# 02A-003.net
KiCad netlist of a schematic drawn in EAGLE
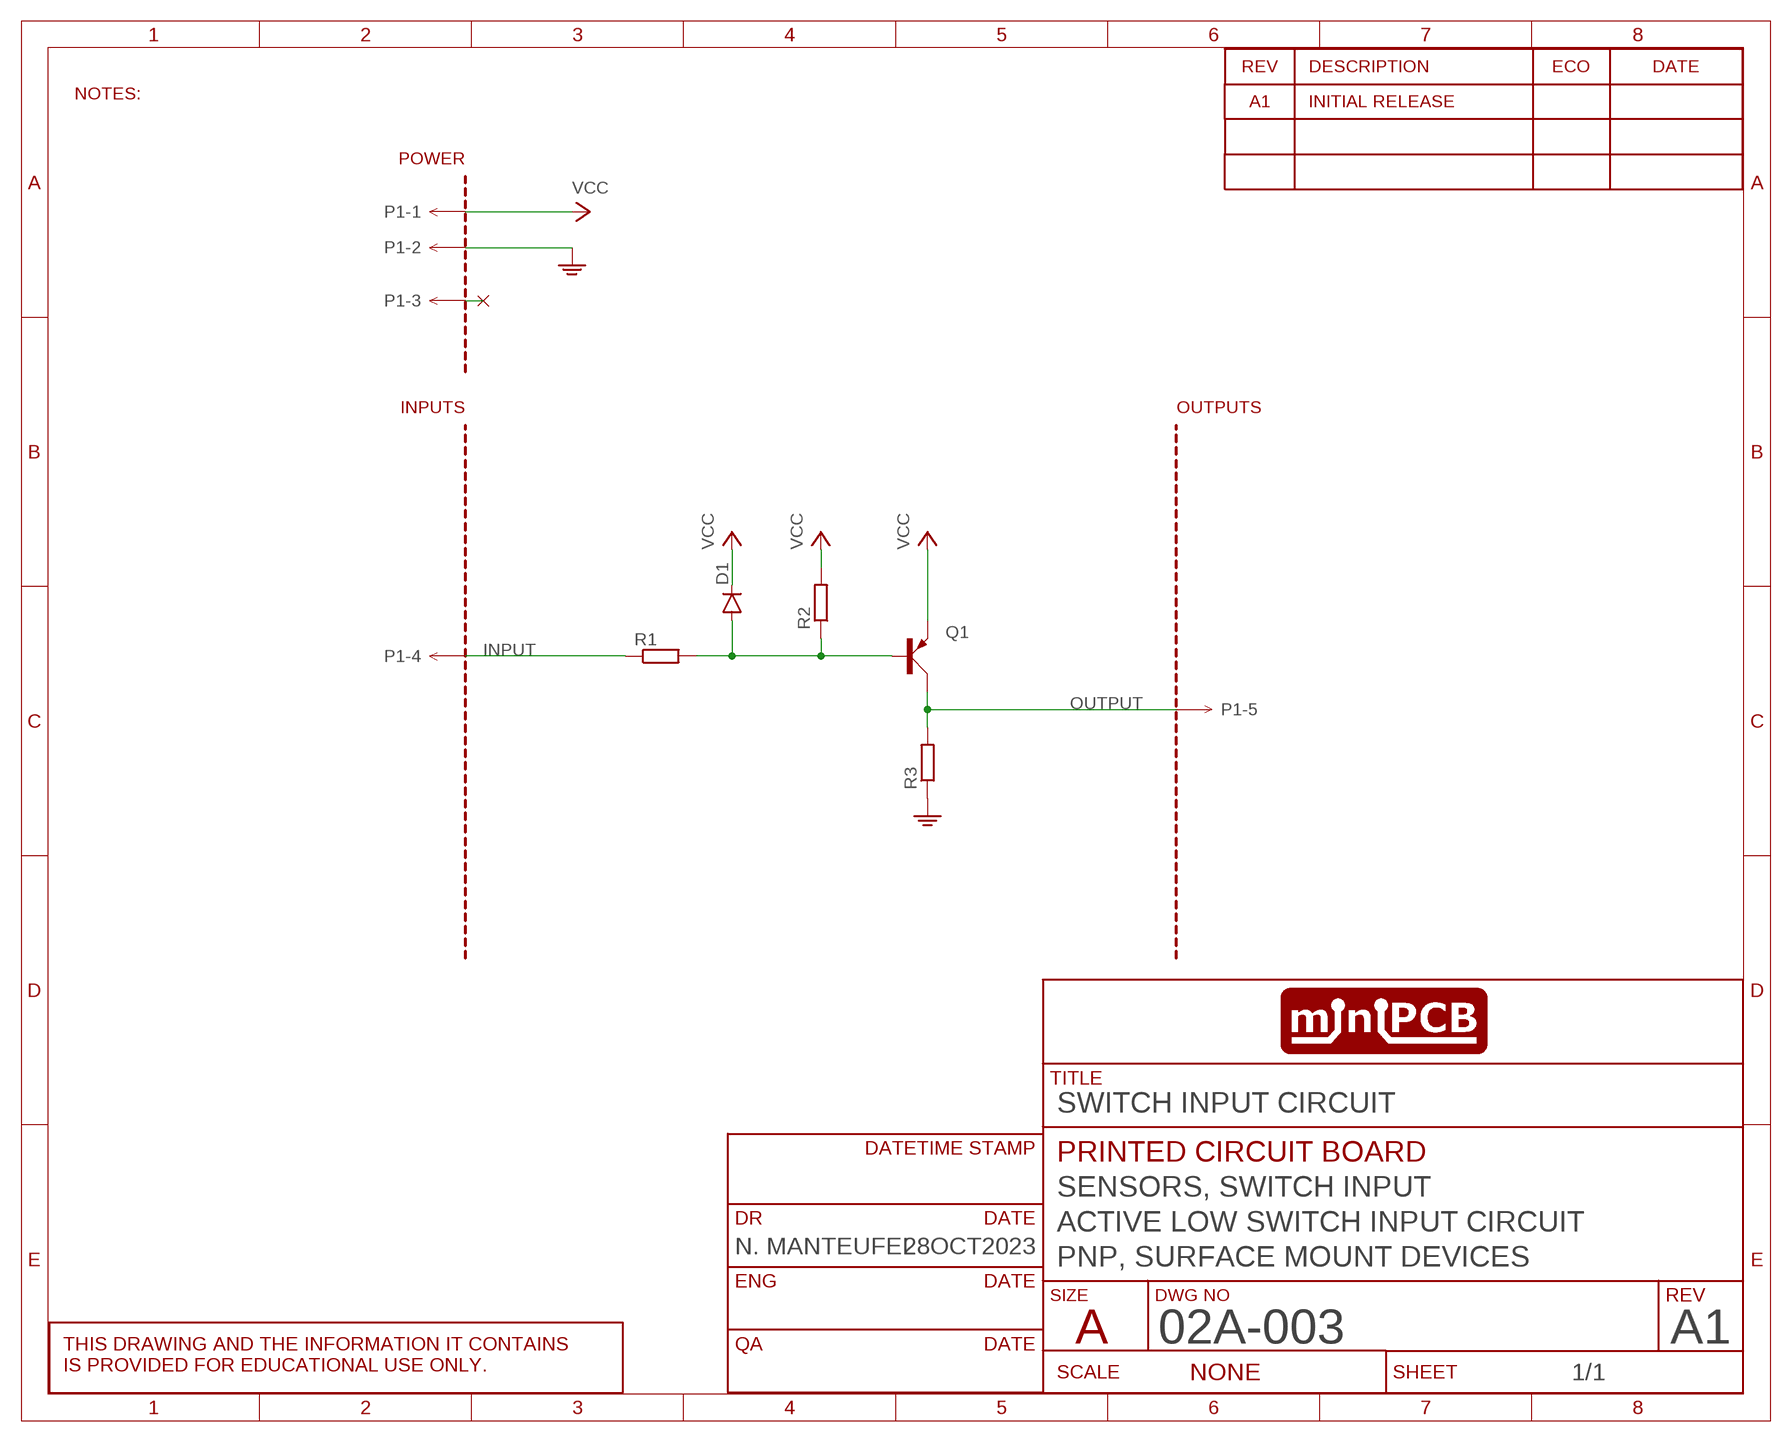
[diagram p0: schematic, sheet 1]

(export (version "E")
  (design (tool "Eeschema 10.0.6"))
  (components
    (comp (ref "D1")
      (value "DIODESMD")
      (footprint "eagle-import:DO214AC")
      (libsource (lib "eagle-import") (part "DIODESMD"))
    )
    (comp (ref "P1")
      (value "MINIPCB_5P5P")
      (footprint "eagle-import:PINS_1X5")
      (libsource (lib "eagle-import") (part "MINIPCB_5P5P"))
    )
    (comp (ref "PCB1")
      (value "MINIPCB_0P00A-20X25")
      (footprint "eagle-import:MINIPCB_00A_20X25")
      (fields (field (name "PART_NUMBER") "02A-003"))
      (libsource (lib "eagle-import") (part "MINIPCB_0P00A-20X25"))
    )
    (comp (ref "Q1")
      (value "BJT_PNPBEC")
      (footprint "eagle-import:SOT23")
      (libsource (lib "eagle-import") (part "BJT_PNPBEC"))
    )
    (comp (ref "R1")
      (value "RESISTORSMD")
      (footprint "eagle-import:R0805")
      (libsource (lib "eagle-import") (part "RESISTORSMD"))
    )
    (comp (ref "R2")
      (value "RESISTORSMD")
      (footprint "eagle-import:R0805")
      (libsource (lib "eagle-import") (part "RESISTORSMD"))
    )
    (comp (ref "R3")
      (value "RESISTORSMD")
      (footprint "eagle-import:R0805")
      (libsource (lib "eagle-import") (part "RESISTORSMD"))
    )
  )
  (nets
    (net (code "1") (name "/INPUT") (class "Default")
      (node (ref "P1") (pin "4") (pinfunction "1_4") (pintype "bidirectional"))
      (node (ref "R1") (pin "1") (pinfunction "1_1") (pintype "passive"))
    )
    (net (code "2") (name "/OUTPUT") (class "Default")
      (node (ref "P1") (pin "5") (pinfunction "1_5") (pintype "bidirectional"))
      (node (ref "Q1") (pin "3") (pinfunction "C_3") (pintype "passive"))
      (node (ref "R3") (pin "2") (pinfunction "2_2") (pintype "passive"))
    )
    (net (code "3") (name "GND") (class "Default")
      (node (ref "P1") (pin "2") (pinfunction "1_2") (pintype "bidirectional"))
      (node (ref "R3") (pin "1") (pinfunction "1_1") (pintype "passive"))
    )
    (net (code "4") (name "Net-(Q1-B)") (class "Default")
      (node (ref "D1") (pin "A") (pinfunction "A_A") (pintype "passive"))
      (node (ref "Q1") (pin "1") (pinfunction "B_1") (pintype "passive"))
      (node (ref "R1") (pin "2") (pinfunction "2_2") (pintype "passive"))
      (node (ref "R2") (pin "1") (pinfunction "1_1") (pintype "passive"))
    )
    (net (code "5") (name "VCC") (class "Default")
      (node (ref "D1") (pin "C") (pinfunction "C_C") (pintype "passive"))
      (node (ref "P1") (pin "1") (pinfunction "1_1") (pintype "bidirectional"))
      (node (ref "Q1") (pin "2") (pinfunction "E_2") (pintype "passive"))
      (node (ref "R2") (pin "2") (pinfunction "2_2") (pintype "passive"))
    )
    (net (code "6") (name "unconnected-(P1C-1-Pad3)") (class "Default")
      (node (ref "P1") (pin "3") (pinfunction "1_3") (pintype "bidirectional"))
    )
  )
)
